# R.net
KiCad netlist of a schematic drawn in Altium Designer
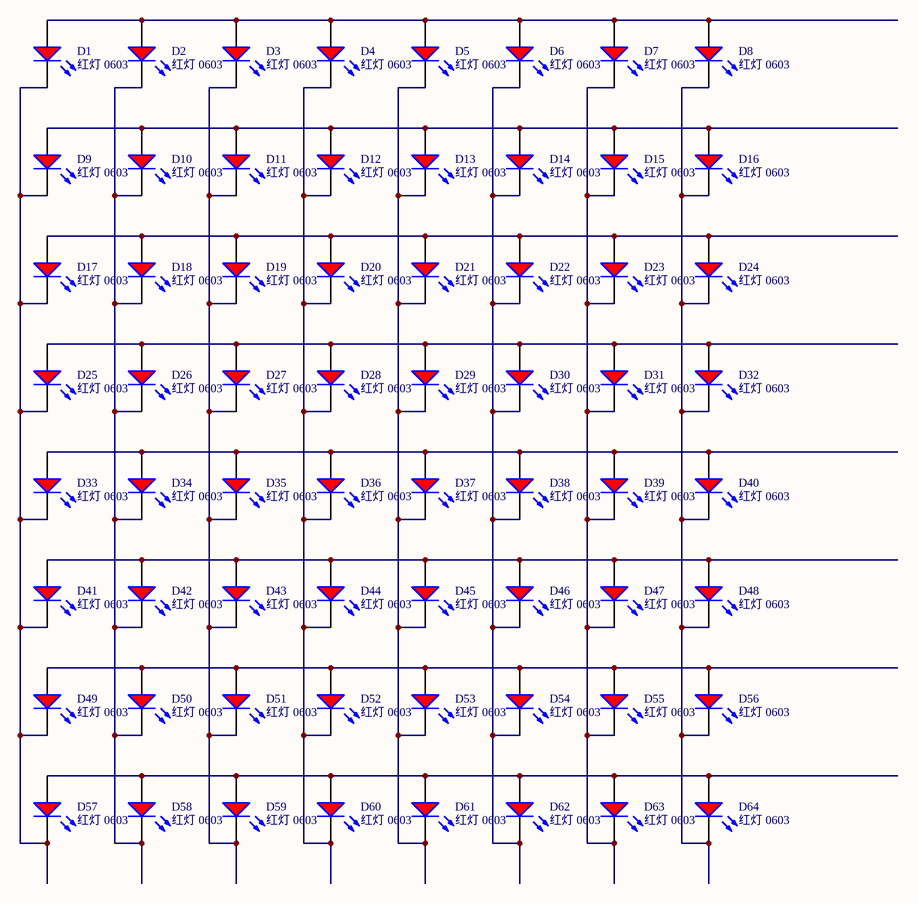
[diagram p0: R.SchDoc]

(export (version "E")
  (design (tool "Eeschema 10.0.6"))
  (components
    (comp (ref "D1")
      (value "红灯 0603")
      (footprint "0603_LED_S1")
      (description "发光二极管")
      (libsource (lib "Miscellaneous Devices LC") (part "0603 红灯"))
    )
    (comp (ref "D2")
      (value "红灯 0603")
      (footprint "0603_LED_S1")
      (description "发光二极管")
      (libsource (lib "Miscellaneous Devices LC") (part "0603 红灯"))
    )
    (comp (ref "D3")
      (value "红灯 0603")
      (footprint "0603_LED_S1")
      (description "发光二极管")
      (libsource (lib "Miscellaneous Devices LC") (part "0603 红灯"))
    )
    (comp (ref "D4")
      (value "红灯 0603")
      (footprint "0603_LED_S1")
      (description "发光二极管")
      (libsource (lib "Miscellaneous Devices LC") (part "0603 红灯"))
    )
    (comp (ref "D5")
      (value "红灯 0603")
      (footprint "0603_LED_S1")
      (description "发光二极管")
      (libsource (lib "Miscellaneous Devices LC") (part "0603 红灯"))
    )
    (comp (ref "D6")
      (value "红灯 0603")
      (footprint "0603_LED_S1")
      (description "发光二极管")
      (libsource (lib "Miscellaneous Devices LC") (part "0603 红灯"))
    )
    (comp (ref "D7")
      (value "红灯 0603")
      (footprint "0603_LED_S1")
      (description "发光二极管")
      (libsource (lib "Miscellaneous Devices LC") (part "0603 红灯"))
    )
    (comp (ref "D8")
      (value "红灯 0603")
      (footprint "0603_LED_S1")
      (description "发光二极管")
      (libsource (lib "Miscellaneous Devices LC") (part "0603 红灯"))
    )
    (comp (ref "D9")
      (value "红灯 0603")
      (footprint "0603_LED_S1")
      (description "发光二极管")
      (libsource (lib "Miscellaneous Devices LC") (part "0603 红灯"))
    )
    (comp (ref "D10")
      (value "红灯 0603")
      (footprint "0603_LED_S1")
      (description "发光二极管")
      (libsource (lib "Miscellaneous Devices LC") (part "0603 红灯"))
    )
    (comp (ref "D11")
      (value "红灯 0603")
      (footprint "0603_LED_S1")
      (description "发光二极管")
      (libsource (lib "Miscellaneous Devices LC") (part "0603 红灯"))
    )
    (comp (ref "D12")
      (value "红灯 0603")
      (footprint "0603_LED_S1")
      (description "发光二极管")
      (libsource (lib "Miscellaneous Devices LC") (part "0603 红灯"))
    )
    (comp (ref "D13")
      (value "红灯 0603")
      (footprint "0603_LED_S1")
      (description "发光二极管")
      (libsource (lib "Miscellaneous Devices LC") (part "0603 红灯"))
    )
    (comp (ref "D14")
      (value "红灯 0603")
      (footprint "0603_LED_S1")
      (description "发光二极管")
      (libsource (lib "Miscellaneous Devices LC") (part "0603 红灯"))
    )
    (comp (ref "D15")
      (value "红灯 0603")
      (footprint "0603_LED_S1")
      (description "发光二极管")
      (libsource (lib "Miscellaneous Devices LC") (part "0603 红灯"))
    )
    (comp (ref "D16")
      (value "红灯 0603")
      (footprint "0603_LED_S1")
      (description "发光二极管")
      (libsource (lib "Miscellaneous Devices LC") (part "0603 红灯"))
    )
    (comp (ref "D17")
      (value "红灯 0603")
      (footprint "0603_LED_S1")
      (description "发光二极管")
      (libsource (lib "Miscellaneous Devices LC") (part "0603 红灯"))
    )
    (comp (ref "D18")
      (value "红灯 0603")
      (footprint "0603_LED_S1")
      (description "发光二极管")
      (libsource (lib "Miscellaneous Devices LC") (part "0603 红灯"))
    )
    (comp (ref "D19")
      (value "红灯 0603")
      (footprint "0603_LED_S1")
      (description "发光二极管")
      (libsource (lib "Miscellaneous Devices LC") (part "0603 红灯"))
    )
    (comp (ref "D20")
      (value "红灯 0603")
      (footprint "0603_LED_S1")
      (description "发光二极管")
      (libsource (lib "Miscellaneous Devices LC") (part "0603 红灯"))
    )
    (comp (ref "D21")
      (value "红灯 0603")
      (footprint "0603_LED_S1")
      (description "发光二极管")
      (libsource (lib "Miscellaneous Devices LC") (part "0603 红灯"))
    )
    (comp (ref "D22")
      (value "红灯 0603")
      (footprint "0603_LED_S1")
      (description "发光二极管")
      (libsource (lib "Miscellaneous Devices LC") (part "0603 红灯"))
    )
    (comp (ref "D23")
      (value "红灯 0603")
      (footprint "0603_LED_S1")
      (description "发光二极管")
      (libsource (lib "Miscellaneous Devices LC") (part "0603 红灯"))
    )
    (comp (ref "D24")
      (value "红灯 0603")
      (footprint "0603_LED_S1")
      (description "发光二极管")
      (libsource (lib "Miscellaneous Devices LC") (part "0603 红灯"))
    )
    (comp (ref "D25")
      (value "红灯 0603")
      (footprint "0603_LED_S1")
      (description "发光二极管")
      (libsource (lib "Miscellaneous Devices LC") (part "0603 红灯"))
    )
    (comp (ref "D26")
      (value "红灯 0603")
      (footprint "0603_LED_S1")
      (description "发光二极管")
      (libsource (lib "Miscellaneous Devices LC") (part "0603 红灯"))
    )
    (comp (ref "D27")
      (value "红灯 0603")
      (footprint "0603_LED_S1")
      (description "发光二极管")
      (libsource (lib "Miscellaneous Devices LC") (part "0603 红灯"))
    )
    (comp (ref "D28")
      (value "红灯 0603")
      (footprint "0603_LED_S1")
      (description "发光二极管")
      (libsource (lib "Miscellaneous Devices LC") (part "0603 红灯"))
    )
    (comp (ref "D29")
      (value "红灯 0603")
      (footprint "0603_LED_S1")
      (description "发光二极管")
      (libsource (lib "Miscellaneous Devices LC") (part "0603 红灯"))
    )
    (comp (ref "D30")
      (value "红灯 0603")
      (footprint "0603_LED_S1")
      (description "发光二极管")
      (libsource (lib "Miscellaneous Devices LC") (part "0603 红灯"))
    )
    (comp (ref "D31")
      (value "红灯 0603")
      (footprint "0603_LED_S1")
      (description "发光二极管")
      (libsource (lib "Miscellaneous Devices LC") (part "0603 红灯"))
    )
    (comp (ref "D32")
      (value "红灯 0603")
      (footprint "0603_LED_S1")
      (description "发光二极管")
      (libsource (lib "Miscellaneous Devices LC") (part "0603 红灯"))
    )
    (comp (ref "D33")
      (value "红灯 0603")
      (footprint "0603_LED_S1")
      (description "发光二极管")
      (libsource (lib "Miscellaneous Devices LC") (part "0603 红灯"))
    )
    (comp (ref "D34")
      (value "红灯 0603")
      (footprint "0603_LED_S1")
      (description "发光二极管")
      (libsource (lib "Miscellaneous Devices LC") (part "0603 红灯"))
    )
    (comp (ref "D35")
      (value "红灯 0603")
      (footprint "0603_LED_S1")
      (description "发光二极管")
      (libsource (lib "Miscellaneous Devices LC") (part "0603 红灯"))
    )
    (comp (ref "D36")
      (value "红灯 0603")
      (footprint "0603_LED_S1")
      (description "发光二极管")
      (libsource (lib "Miscellaneous Devices LC") (part "0603 红灯"))
    )
    (comp (ref "D37")
      (value "红灯 0603")
      (footprint "0603_LED_S1")
      (description "发光二极管")
      (libsource (lib "Miscellaneous Devices LC") (part "0603 红灯"))
    )
    (comp (ref "D38")
      (value "红灯 0603")
      (footprint "0603_LED_S1")
      (description "发光二极管")
      (libsource (lib "Miscellaneous Devices LC") (part "0603 红灯"))
    )
    (comp (ref "D39")
      (value "红灯 0603")
      (footprint "0603_LED_S1")
      (description "发光二极管")
      (libsource (lib "Miscellaneous Devices LC") (part "0603 红灯"))
    )
    (comp (ref "D40")
      (value "红灯 0603")
      (footprint "0603_LED_S1")
      (description "发光二极管")
      (libsource (lib "Miscellaneous Devices LC") (part "0603 红灯"))
    )
    (comp (ref "D41")
      (value "红灯 0603")
      (footprint "0603_LED_S1")
      (description "发光二极管")
      (libsource (lib "Miscellaneous Devices LC") (part "0603 红灯"))
    )
    (comp (ref "D42")
      (value "红灯 0603")
      (footprint "0603_LED_S1")
      (description "发光二极管")
      (libsource (lib "Miscellaneous Devices LC") (part "0603 红灯"))
    )
    (comp (ref "D43")
      (value "红灯 0603")
      (footprint "0603_LED_S1")
      (description "发光二极管")
      (libsource (lib "Miscellaneous Devices LC") (part "0603 红灯"))
    )
    (comp (ref "D44")
      (value "红灯 0603")
      (footprint "0603_LED_S1")
      (description "发光二极管")
      (libsource (lib "Miscellaneous Devices LC") (part "0603 红灯"))
    )
    (comp (ref "D45")
      (value "红灯 0603")
      (footprint "0603_LED_S1")
      (description "发光二极管")
      (libsource (lib "Miscellaneous Devices LC") (part "0603 红灯"))
    )
    (comp (ref "D46")
      (value "红灯 0603")
      (footprint "0603_LED_S1")
      (description "发光二极管")
      (libsource (lib "Miscellaneous Devices LC") (part "0603 红灯"))
    )
    (comp (ref "D47")
      (value "红灯 0603")
      (footprint "0603_LED_S1")
      (description "发光二极管")
      (libsource (lib "Miscellaneous Devices LC") (part "0603 红灯"))
    )
    (comp (ref "D48")
      (value "红灯 0603")
      (footprint "0603_LED_S1")
      (description "发光二极管")
      (libsource (lib "Miscellaneous Devices LC") (part "0603 红灯"))
    )
    (comp (ref "D49")
      (value "红灯 0603")
      (footprint "0603_LED_S1")
      (description "发光二极管")
      (libsource (lib "Miscellaneous Devices LC") (part "0603 红灯"))
    )
    (comp (ref "D50")
      (value "红灯 0603")
      (footprint "0603_LED_S1")
      (description "发光二极管")
      (libsource (lib "Miscellaneous Devices LC") (part "0603 红灯"))
    )
    (comp (ref "D51")
      (value "红灯 0603")
      (footprint "0603_LED_S1")
      (description "发光二极管")
      (libsource (lib "Miscellaneous Devices LC") (part "0603 红灯"))
    )
    (comp (ref "D52")
      (value "红灯 0603")
      (footprint "0603_LED_S1")
      (description "发光二极管")
      (libsource (lib "Miscellaneous Devices LC") (part "0603 红灯"))
    )
    (comp (ref "D53")
      (value "红灯 0603")
      (footprint "0603_LED_S1")
      (description "发光二极管")
      (libsource (lib "Miscellaneous Devices LC") (part "0603 红灯"))
    )
    (comp (ref "D54")
      (value "红灯 0603")
      (footprint "0603_LED_S1")
      (description "发光二极管")
      (libsource (lib "Miscellaneous Devices LC") (part "0603 红灯"))
    )
    (comp (ref "D55")
      (value "红灯 0603")
      (footprint "0603_LED_S1")
      (description "发光二极管")
      (libsource (lib "Miscellaneous Devices LC") (part "0603 红灯"))
    )
    (comp (ref "D56")
      (value "红灯 0603")
      (footprint "0603_LED_S1")
      (description "发光二极管")
      (libsource (lib "Miscellaneous Devices LC") (part "0603 红灯"))
    )
    (comp (ref "D57")
      (value "红灯 0603")
      (footprint "0603_LED_S1")
      (description "发光二极管")
      (libsource (lib "Miscellaneous Devices LC") (part "0603 红灯"))
    )
    (comp (ref "D58")
      (value "红灯 0603")
      (footprint "0603_LED_S1")
      (description "发光二极管")
      (libsource (lib "Miscellaneous Devices LC") (part "0603 红灯"))
    )
    (comp (ref "D59")
      (value "红灯 0603")
      (footprint "0603_LED_S1")
      (description "发光二极管")
      (libsource (lib "Miscellaneous Devices LC") (part "0603 红灯"))
    )
    (comp (ref "D60")
      (value "红灯 0603")
      (footprint "0603_LED_S1")
      (description "发光二极管")
      (libsource (lib "Miscellaneous Devices LC") (part "0603 红灯"))
    )
    (comp (ref "D61")
      (value "红灯 0603")
      (footprint "0603_LED_S1")
      (description "发光二极管")
      (libsource (lib "Miscellaneous Devices LC") (part "0603 红灯"))
    )
    (comp (ref "D62")
      (value "红灯 0603")
      (footprint "0603_LED_S1")
      (description "发光二极管")
      (libsource (lib "Miscellaneous Devices LC") (part "0603 红灯"))
    )
    (comp (ref "D63")
      (value "红灯 0603")
      (footprint "0603_LED_S1")
      (description "发光二极管")
      (libsource (lib "Miscellaneous Devices LC") (part "0603 红灯"))
    )
    (comp (ref "D64")
      (value "红灯 0603")
      (footprint "0603_LED_S1")
      (description "发光二极管")
      (libsource (lib "Miscellaneous Devices LC") (part "0603 红灯"))
    )
  )
  (nets
    (net (code "1") (name "Net-(D1-PadA)") (class "Default")
      (node (ref "D1") (pin "A") (pinfunction "A_A") (pintype "passive"))
      (node (ref "D2") (pin "A") (pinfunction "A_A") (pintype "passive"))
      (node (ref "D3") (pin "A") (pinfunction "A_A") (pintype "passive"))
      (node (ref "D4") (pin "A") (pinfunction "A_A") (pintype "passive"))
      (node (ref "D5") (pin "A") (pinfunction "A_A") (pintype "passive"))
      (node (ref "D6") (pin "A") (pinfunction "A_A") (pintype "passive"))
      (node (ref "D7") (pin "A") (pinfunction "A_A") (pintype "passive"))
      (node (ref "D8") (pin "A") (pinfunction "A_A") (pintype "passive"))
    )
    (net (code "2") (name "Net-(D1-PadK)") (class "Default")
      (node (ref "D1") (pin "K") (pinfunction "K_K") (pintype "passive"))
      (node (ref "D17") (pin "K") (pinfunction "K_K") (pintype "passive"))
      (node (ref "D25") (pin "K") (pinfunction "K_K") (pintype "passive"))
      (node (ref "D33") (pin "K") (pinfunction "K_K") (pintype "passive"))
      (node (ref "D41") (pin "K") (pinfunction "K_K") (pintype "passive"))
      (node (ref "D49") (pin "K") (pinfunction "K_K") (pintype "passive"))
      (node (ref "D57") (pin "K") (pinfunction "K_K") (pintype "passive"))
      (node (ref "D9") (pin "K") (pinfunction "K_K") (pintype "passive"))
    )
    (net (code "3") (name "Net-(D10-PadA)") (class "Default")
      (node (ref "D10") (pin "A") (pinfunction "A_A") (pintype "passive"))
      (node (ref "D11") (pin "A") (pinfunction "A_A") (pintype "passive"))
      (node (ref "D12") (pin "A") (pinfunction "A_A") (pintype "passive"))
      (node (ref "D13") (pin "A") (pinfunction "A_A") (pintype "passive"))
      (node (ref "D14") (pin "A") (pinfunction "A_A") (pintype "passive"))
      (node (ref "D15") (pin "A") (pinfunction "A_A") (pintype "passive"))
      (node (ref "D16") (pin "A") (pinfunction "A_A") (pintype "passive"))
      (node (ref "D9") (pin "A") (pinfunction "A_A") (pintype "passive"))
    )
    (net (code "4") (name "Net-(D10-PadK)") (class "Default")
      (node (ref "D10") (pin "K") (pinfunction "K_K") (pintype "passive"))
      (node (ref "D18") (pin "K") (pinfunction "K_K") (pintype "passive"))
      (node (ref "D2") (pin "K") (pinfunction "K_K") (pintype "passive"))
      (node (ref "D26") (pin "K") (pinfunction "K_K") (pintype "passive"))
      (node (ref "D34") (pin "K") (pinfunction "K_K") (pintype "passive"))
      (node (ref "D42") (pin "K") (pinfunction "K_K") (pintype "passive"))
      (node (ref "D50") (pin "K") (pinfunction "K_K") (pintype "passive"))
      (node (ref "D58") (pin "K") (pinfunction "K_K") (pintype "passive"))
    )
    (net (code "5") (name "Net-(D11-PadK)") (class "Default")
      (node (ref "D11") (pin "K") (pinfunction "K_K") (pintype "passive"))
      (node (ref "D19") (pin "K") (pinfunction "K_K") (pintype "passive"))
      (node (ref "D27") (pin "K") (pinfunction "K_K") (pintype "passive"))
      (node (ref "D3") (pin "K") (pinfunction "K_K") (pintype "passive"))
      (node (ref "D35") (pin "K") (pinfunction "K_K") (pintype "passive"))
      (node (ref "D43") (pin "K") (pinfunction "K_K") (pintype "passive"))
      (node (ref "D51") (pin "K") (pinfunction "K_K") (pintype "passive"))
      (node (ref "D59") (pin "K") (pinfunction "K_K") (pintype "passive"))
    )
    (net (code "6") (name "Net-(D12-PadK)") (class "Default")
      (node (ref "D12") (pin "K") (pinfunction "K_K") (pintype "passive"))
      (node (ref "D20") (pin "K") (pinfunction "K_K") (pintype "passive"))
      (node (ref "D28") (pin "K") (pinfunction "K_K") (pintype "passive"))
      (node (ref "D36") (pin "K") (pinfunction "K_K") (pintype "passive"))
      (node (ref "D4") (pin "K") (pinfunction "K_K") (pintype "passive"))
      (node (ref "D44") (pin "K") (pinfunction "K_K") (pintype "passive"))
      (node (ref "D52") (pin "K") (pinfunction "K_K") (pintype "passive"))
      (node (ref "D60") (pin "K") (pinfunction "K_K") (pintype "passive"))
    )
    (net (code "7") (name "Net-(D13-PadK)") (class "Default")
      (node (ref "D13") (pin "K") (pinfunction "K_K") (pintype "passive"))
      (node (ref "D21") (pin "K") (pinfunction "K_K") (pintype "passive"))
      (node (ref "D29") (pin "K") (pinfunction "K_K") (pintype "passive"))
      (node (ref "D37") (pin "K") (pinfunction "K_K") (pintype "passive"))
      (node (ref "D45") (pin "K") (pinfunction "K_K") (pintype "passive"))
      (node (ref "D5") (pin "K") (pinfunction "K_K") (pintype "passive"))
      (node (ref "D53") (pin "K") (pinfunction "K_K") (pintype "passive"))
      (node (ref "D61") (pin "K") (pinfunction "K_K") (pintype "passive"))
    )
    (net (code "8") (name "Net-(D14-PadK)") (class "Default")
      (node (ref "D14") (pin "K") (pinfunction "K_K") (pintype "passive"))
      (node (ref "D22") (pin "K") (pinfunction "K_K") (pintype "passive"))
      (node (ref "D30") (pin "K") (pinfunction "K_K") (pintype "passive"))
      (node (ref "D38") (pin "K") (pinfunction "K_K") (pintype "passive"))
      (node (ref "D46") (pin "K") (pinfunction "K_K") (pintype "passive"))
      (node (ref "D54") (pin "K") (pinfunction "K_K") (pintype "passive"))
      (node (ref "D6") (pin "K") (pinfunction "K_K") (pintype "passive"))
      (node (ref "D62") (pin "K") (pinfunction "K_K") (pintype "passive"))
    )
    (net (code "9") (name "Net-(D15-PadK)") (class "Default")
      (node (ref "D15") (pin "K") (pinfunction "K_K") (pintype "passive"))
      (node (ref "D23") (pin "K") (pinfunction "K_K") (pintype "passive"))
      (node (ref "D31") (pin "K") (pinfunction "K_K") (pintype "passive"))
      (node (ref "D39") (pin "K") (pinfunction "K_K") (pintype "passive"))
      (node (ref "D47") (pin "K") (pinfunction "K_K") (pintype "passive"))
      (node (ref "D55") (pin "K") (pinfunction "K_K") (pintype "passive"))
      (node (ref "D63") (pin "K") (pinfunction "K_K") (pintype "passive"))
      (node (ref "D7") (pin "K") (pinfunction "K_K") (pintype "passive"))
    )
    (net (code "10") (name "Net-(D16-PadK)") (class "Default")
      (node (ref "D16") (pin "K") (pinfunction "K_K") (pintype "passive"))
      (node (ref "D24") (pin "K") (pinfunction "K_K") (pintype "passive"))
      (node (ref "D32") (pin "K") (pinfunction "K_K") (pintype "passive"))
      (node (ref "D40") (pin "K") (pinfunction "K_K") (pintype "passive"))
      (node (ref "D48") (pin "K") (pinfunction "K_K") (pintype "passive"))
      (node (ref "D56") (pin "K") (pinfunction "K_K") (pintype "passive"))
      (node (ref "D64") (pin "K") (pinfunction "K_K") (pintype "passive"))
      (node (ref "D8") (pin "K") (pinfunction "K_K") (pintype "passive"))
    )
    (net (code "11") (name "Net-(D17-PadA)") (class "Default")
      (node (ref "D17") (pin "A") (pinfunction "A_A") (pintype "passive"))
      (node (ref "D18") (pin "A") (pinfunction "A_A") (pintype "passive"))
      (node (ref "D19") (pin "A") (pinfunction "A_A") (pintype "passive"))
      (node (ref "D20") (pin "A") (pinfunction "A_A") (pintype "passive"))
      (node (ref "D21") (pin "A") (pinfunction "A_A") (pintype "passive"))
      (node (ref "D22") (pin "A") (pinfunction "A_A") (pintype "passive"))
      (node (ref "D23") (pin "A") (pinfunction "A_A") (pintype "passive"))
      (node (ref "D24") (pin "A") (pinfunction "A_A") (pintype "passive"))
    )
    (net (code "12") (name "Net-(D25-PadA)") (class "Default")
      (node (ref "D25") (pin "A") (pinfunction "A_A") (pintype "passive"))
      (node (ref "D26") (pin "A") (pinfunction "A_A") (pintype "passive"))
      (node (ref "D27") (pin "A") (pinfunction "A_A") (pintype "passive"))
      (node (ref "D28") (pin "A") (pinfunction "A_A") (pintype "passive"))
      (node (ref "D29") (pin "A") (pinfunction "A_A") (pintype "passive"))
      (node (ref "D30") (pin "A") (pinfunction "A_A") (pintype "passive"))
      (node (ref "D31") (pin "A") (pinfunction "A_A") (pintype "passive"))
      (node (ref "D32") (pin "A") (pinfunction "A_A") (pintype "passive"))
    )
    (net (code "13") (name "Net-(D33-PadA)") (class "Default")
      (node (ref "D33") (pin "A") (pinfunction "A_A") (pintype "passive"))
      (node (ref "D34") (pin "A") (pinfunction "A_A") (pintype "passive"))
      (node (ref "D35") (pin "A") (pinfunction "A_A") (pintype "passive"))
      (node (ref "D36") (pin "A") (pinfunction "A_A") (pintype "passive"))
      (node (ref "D37") (pin "A") (pinfunction "A_A") (pintype "passive"))
      (node (ref "D38") (pin "A") (pinfunction "A_A") (pintype "passive"))
      (node (ref "D39") (pin "A") (pinfunction "A_A") (pintype "passive"))
      (node (ref "D40") (pin "A") (pinfunction "A_A") (pintype "passive"))
    )
    (net (code "14") (name "Net-(D41-PadA)") (class "Default")
      (node (ref "D41") (pin "A") (pinfunction "A_A") (pintype "passive"))
      (node (ref "D42") (pin "A") (pinfunction "A_A") (pintype "passive"))
      (node (ref "D43") (pin "A") (pinfunction "A_A") (pintype "passive"))
      (node (ref "D44") (pin "A") (pinfunction "A_A") (pintype "passive"))
      (node (ref "D45") (pin "A") (pinfunction "A_A") (pintype "passive"))
      (node (ref "D46") (pin "A") (pinfunction "A_A") (pintype "passive"))
      (node (ref "D47") (pin "A") (pinfunction "A_A") (pintype "passive"))
      (node (ref "D48") (pin "A") (pinfunction "A_A") (pintype "passive"))
    )
    (net (code "15") (name "Net-(D49-PadA)") (class "Default")
      (node (ref "D49") (pin "A") (pinfunction "A_A") (pintype "passive"))
      (node (ref "D50") (pin "A") (pinfunction "A_A") (pintype "passive"))
      (node (ref "D51") (pin "A") (pinfunction "A_A") (pintype "passive"))
      (node (ref "D52") (pin "A") (pinfunction "A_A") (pintype "passive"))
      (node (ref "D53") (pin "A") (pinfunction "A_A") (pintype "passive"))
      (node (ref "D54") (pin "A") (pinfunction "A_A") (pintype "passive"))
      (node (ref "D55") (pin "A") (pinfunction "A_A") (pintype "passive"))
      (node (ref "D56") (pin "A") (pinfunction "A_A") (pintype "passive"))
    )
    (net (code "16") (name "Net-(D57-PadA)") (class "Default")
      (node (ref "D57") (pin "A") (pinfunction "A_A") (pintype "passive"))
      (node (ref "D58") (pin "A") (pinfunction "A_A") (pintype "passive"))
      (node (ref "D59") (pin "A") (pinfunction "A_A") (pintype "passive"))
      (node (ref "D60") (pin "A") (pinfunction "A_A") (pintype "passive"))
      (node (ref "D61") (pin "A") (pinfunction "A_A") (pintype "passive"))
      (node (ref "D62") (pin "A") (pinfunction "A_A") (pintype "passive"))
      (node (ref "D63") (pin "A") (pinfunction "A_A") (pintype "passive"))
      (node (ref "D64") (pin "A") (pinfunction "A_A") (pintype "passive"))
    )
  )
)
